# 05_FPGA_SOC_Part1.net
KiCad netlist of a schematic drawn in Altium Designer
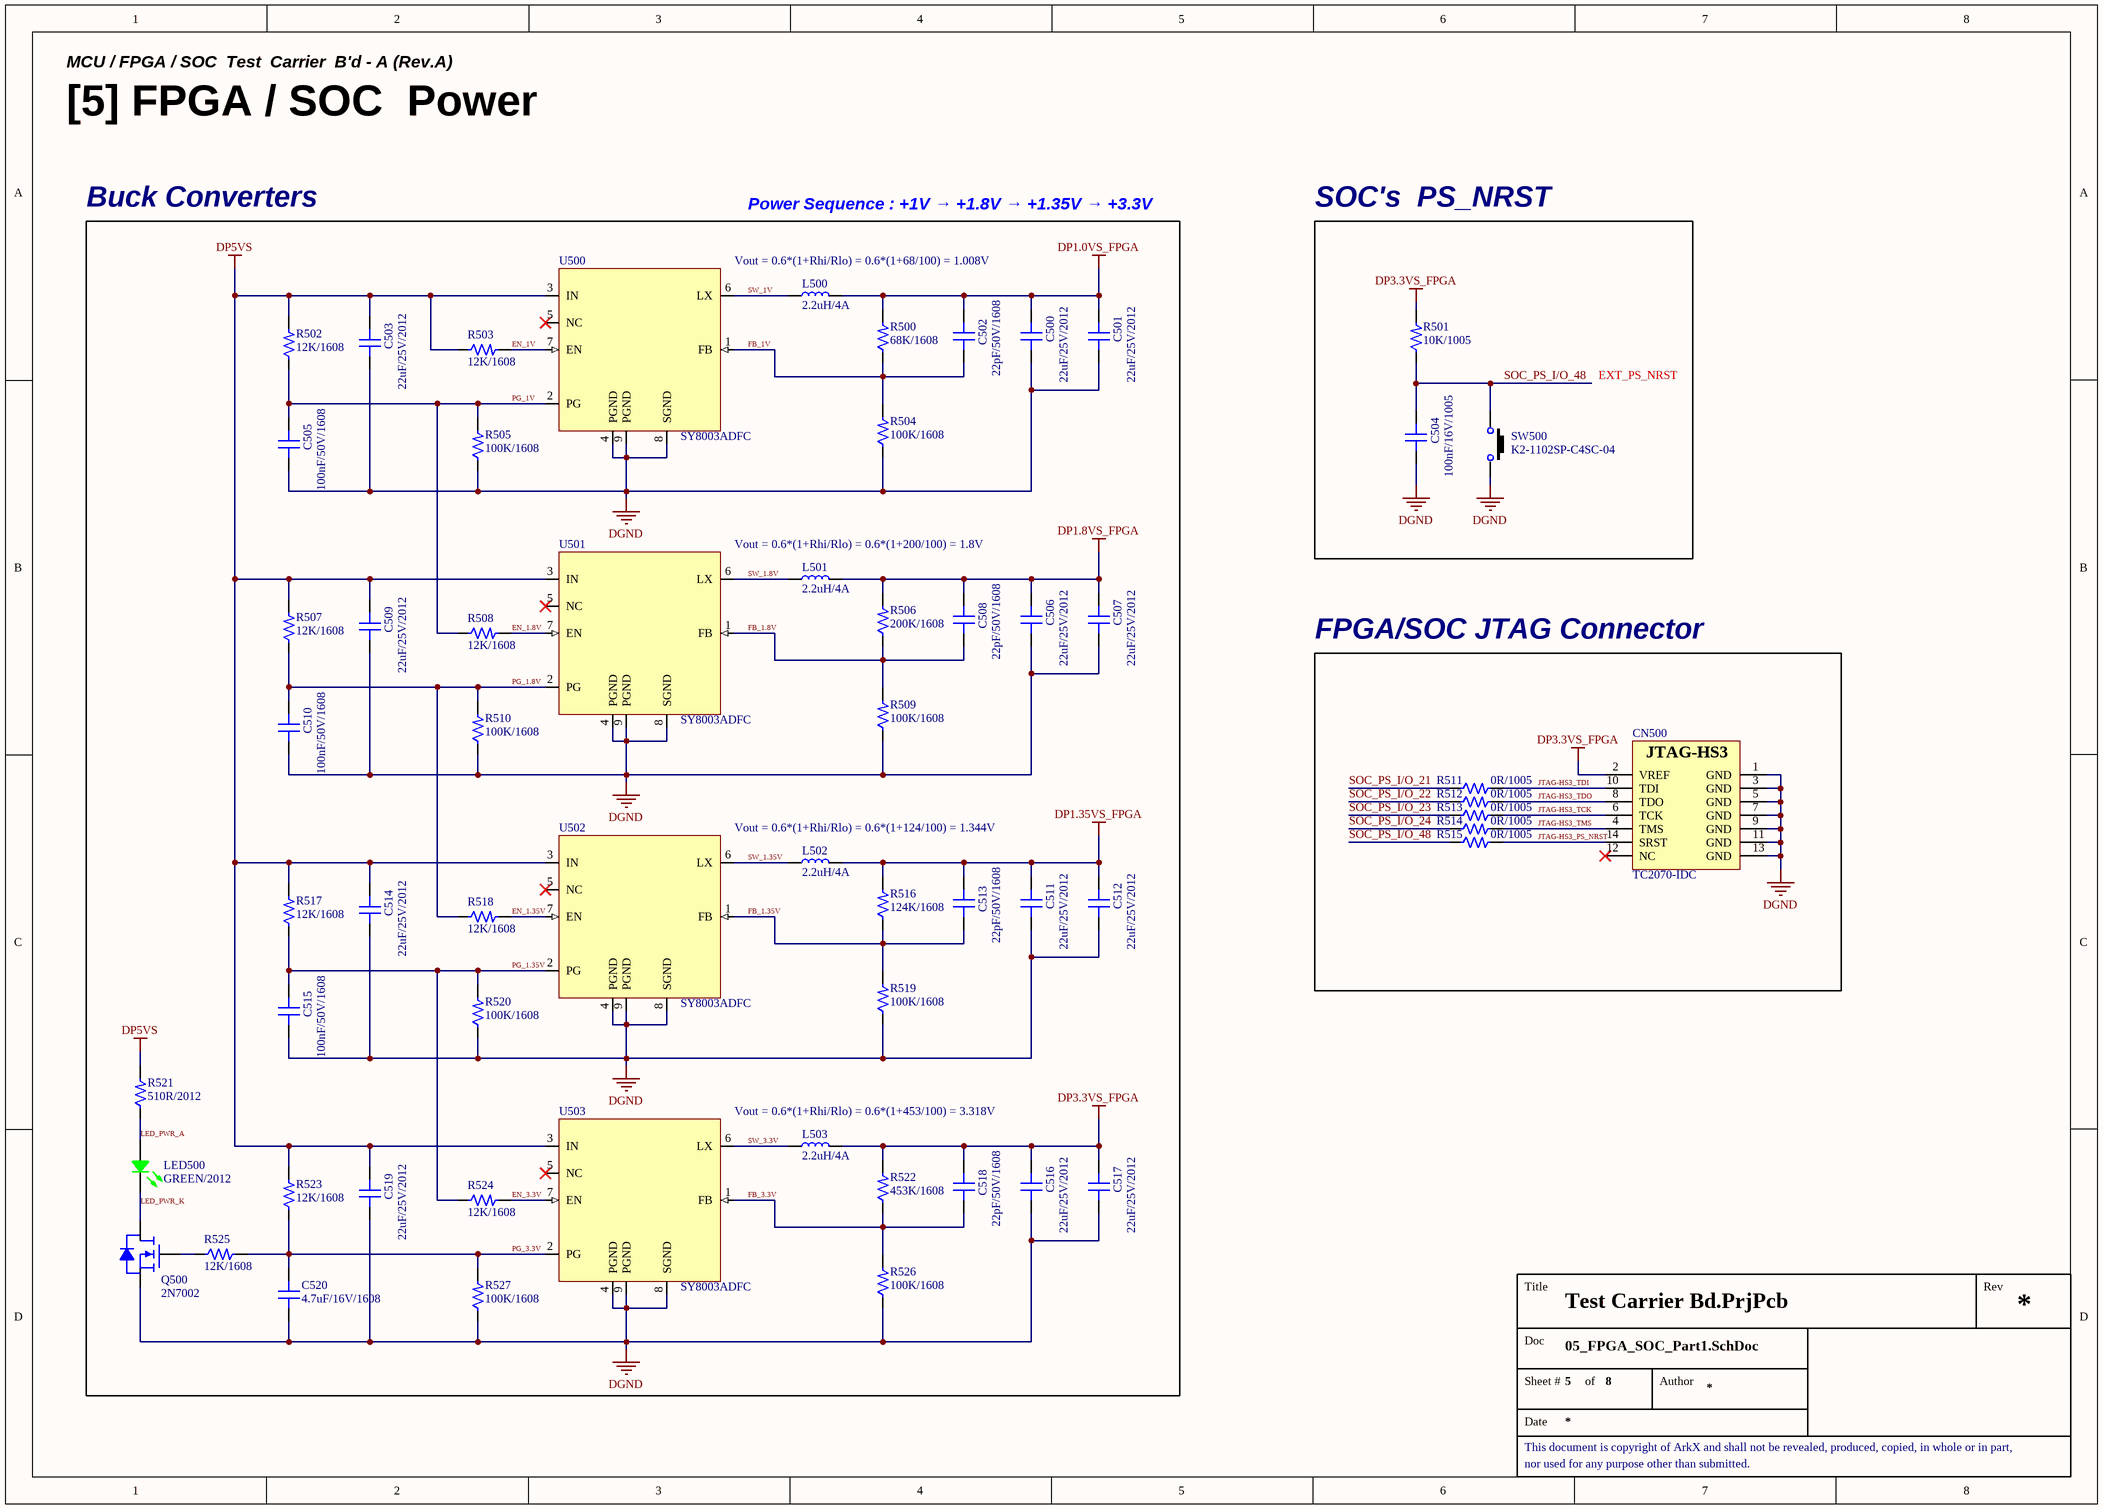
[diagram p0: 05_FPGA_SOC_Part1.SchDoc]

(export (version "E")
  (design (tool "Eeschema 10.0.6"))
  (components
    (comp (ref "C500")
      (value "22uF/25V/2012")
      (footprint "CAP 2012 (0805_INCH)")
      (description "Ceramic CAP_22uF/25V/2012")
      (fields (field (name "LCSC PART #") "C45783"))
      (libsource (lib "Arkx") (part "CAP_22uF/25V/2012"))
    )
    (comp (ref "C501")
      (value "22uF/25V/2012")
      (footprint "CAP 2012 (0805_INCH)")
      (description "Ceramic CAP_22uF/25V/2012")
      (fields (field (name "LCSC PART #") "C45783"))
      (libsource (lib "Arkx") (part "CAP_22uF/25V/2012"))
    )
    (comp (ref "C502")
      (value "22pF/50V/1608")
      (footprint "CAP 1608 (0603_INCH)")
      (description "Ceramic CAP_22pF/50V/1608")
      (fields (field (name "LCSC PART #") "C1653"))
      (libsource (lib "Arkx") (part "CAP_22pF/50V/1608"))
    )
    (comp (ref "C503")
      (value "22uF/25V/2012")
      (footprint "CAP 2012 (0805_INCH)")
      (description "Ceramic CAP_22uF/25V/2012")
      (fields (field (name "LCSC PART #") "C45783"))
      (libsource (lib "Arkx") (part "CAP_22uF/25V/2012"))
    )
    (comp (ref "C504")
      (value "100nF/16V/1005")
      (footprint "CAP 1005 (0402_INCH)")
      (description "Ceramic CAP_100nF/16V/1005")
      (fields (field (name "LCSC PART #") "C1525"))
      (libsource (lib "Arkx") (part "CAP_100nF/16V/1005"))
    )
    (comp (ref "C505")
      (value "100nF/50V/1608")
      (footprint "CAP 1608 (0603_INCH)")
      (description "Ceramic CAP_100nF/50V/1608")
      (fields (field (name "LCSC PART #") "C14663"))
      (libsource (lib "Arkx") (part "CAP_100nF/50V/1608"))
    )
    (comp (ref "C506")
      (value "22uF/25V/2012")
      (footprint "CAP 2012 (0805_INCH)")
      (description "Ceramic CAP_22uF/25V/2012")
      (fields (field (name "LCSC PART #") "C45783"))
      (libsource (lib "Arkx") (part "CAP_22uF/25V/2012"))
    )
    (comp (ref "C507")
      (value "22uF/25V/2012")
      (footprint "CAP 2012 (0805_INCH)")
      (description "Ceramic CAP_22uF/25V/2012")
      (fields (field (name "LCSC PART #") "C45783"))
      (libsource (lib "Arkx") (part "CAP_22uF/25V/2012"))
    )
    (comp (ref "C508")
      (value "22pF/50V/1608")
      (footprint "CAP 1608 (0603_INCH)")
      (description "Ceramic CAP_22pF/50V/1608")
      (fields (field (name "LCSC PART #") "C1653"))
      (libsource (lib "Arkx") (part "CAP_22pF/50V/1608"))
    )
    (comp (ref "C509")
      (value "22uF/25V/2012")
      (footprint "CAP 2012 (0805_INCH)")
      (description "Ceramic CAP_22uF/25V/2012")
      (fields (field (name "LCSC PART #") "C45783"))
      (libsource (lib "Arkx") (part "CAP_22uF/25V/2012"))
    )
    (comp (ref "C510")
      (value "100nF/50V/1608")
      (footprint "CAP 1608 (0603_INCH)")
      (description "Ceramic CAP_100nF/50V/1608")
      (fields (field (name "LCSC PART #") "C14663"))
      (libsource (lib "Arkx") (part "CAP_100nF/50V/1608"))
    )
    (comp (ref "C511")
      (value "22uF/25V/2012")
      (footprint "CAP 2012 (0805_INCH)")
      (description "Ceramic CAP_22uF/25V/2012")
      (fields (field (name "LCSC PART #") "C45783"))
      (libsource (lib "Arkx") (part "CAP_22uF/25V/2012"))
    )
    (comp (ref "C512")
      (value "22uF/25V/2012")
      (footprint "CAP 2012 (0805_INCH)")
      (description "Ceramic CAP_22uF/25V/2012")
      (fields (field (name "LCSC PART #") "C45783"))
      (libsource (lib "Arkx") (part "CAP_22uF/25V/2012"))
    )
    (comp (ref "C513")
      (value "22pF/50V/1608")
      (footprint "CAP 1608 (0603_INCH)")
      (description "Ceramic CAP_22pF/50V/1608")
      (fields (field (name "LCSC PART #") "C1653"))
      (libsource (lib "Arkx") (part "CAP_22pF/50V/1608"))
    )
    (comp (ref "C514")
      (value "22uF/25V/2012")
      (footprint "CAP 2012 (0805_INCH)")
      (description "Ceramic CAP_22uF/25V/2012")
      (fields (field (name "LCSC PART #") "C45783"))
      (libsource (lib "Arkx") (part "CAP_22uF/25V/2012"))
    )
    (comp (ref "C515")
      (value "100nF/50V/1608")
      (footprint "CAP 1608 (0603_INCH)")
      (description "Ceramic CAP_100nF/50V/1608")
      (fields (field (name "LCSC PART #") "C14663"))
      (libsource (lib "Arkx") (part "CAP_100nF/50V/1608"))
    )
    (comp (ref "C516")
      (value "22uF/25V/2012")
      (footprint "CAP 2012 (0805_INCH)")
      (description "Ceramic CAP_22uF/25V/2012")
      (fields (field (name "LCSC PART #") "C45783"))
      (libsource (lib "Arkx") (part "CAP_22uF/25V/2012"))
    )
    (comp (ref "C517")
      (value "22uF/25V/2012")
      (footprint "CAP 2012 (0805_INCH)")
      (description "Ceramic CAP_22uF/25V/2012")
      (fields (field (name "LCSC PART #") "C45783"))
      (libsource (lib "Arkx") (part "CAP_22uF/25V/2012"))
    )
    (comp (ref "C518")
      (value "22pF/50V/1608")
      (footprint "CAP 1608 (0603_INCH)")
      (description "Ceramic CAP_22pF/50V/1608")
      (fields (field (name "LCSC PART #") "C1653"))
      (libsource (lib "Arkx") (part "CAP_22pF/50V/1608"))
    )
    (comp (ref "C519")
      (value "22uF/25V/2012")
      (footprint "CAP 2012 (0805_INCH)")
      (description "Ceramic CAP_22uF/25V/2012")
      (fields (field (name "LCSC PART #") "C45783"))
      (libsource (lib "Arkx") (part "CAP_22uF/25V/2012"))
    )
    (comp (ref "C520")
      (value "4.7uF/16V/1608")
      (footprint "CAP 1608 (0603_INCH)")
      (description "Ceramic CAP_4.7uF/16V/1608")
      (fields (field (name "LCSC PART #") "C19666"))
      (libsource (lib "Arkx") (part "CAP_4.7uF/16V/1608"))
    )
    (comp (ref "CN500")
      (value "TC2070-IDC")
      (footprint "CON_TC2070-IDC")
      (description "TC2070 14-pin Plug-of-Nails™ (with legs) to 14 pin 2mm female IDC connector.")
      (libsource (lib "Arkx") (part "CON_TC2070-IDC(JTAG-HS3)"))
    )
    (comp (ref "L500")
      (value "2.2uH/4A")
      (footprint "IND_2.2uH/4A/6x6_(BWVS006060282R2M00)")
      (description "FIXED IND 2.2uH 4A 20mohm SMD")
      (fields (field (name "LCSC PART #") "C2838207"))
      (libsource (lib "Arkx") (part "IND_2.2uH/4A/6x6"))
    )
    (comp (ref "L501")
      (value "2.2uH/4A")
      (footprint "IND_2.2uH/4A/6x6_(BWVS006060282R2M00)")
      (description "FIXED IND 2.2uH 4A 20mohm SMD")
      (fields (field (name "LCSC PART #") "C2838207"))
      (libsource (lib "Arkx") (part "IND_2.2uH/4A/6x6"))
    )
    (comp (ref "L502")
      (value "2.2uH/4A")
      (footprint "IND_2.2uH/4A/6x6_(BWVS006060282R2M00)")
      (description "FIXED IND 2.2uH 4A 20mohm SMD")
      (fields (field (name "LCSC PART #") "C2838207"))
      (libsource (lib "Arkx") (part "IND_2.2uH/4A/6x6"))
    )
    (comp (ref "L503")
      (value "2.2uH/4A")
      (footprint "IND_2.2uH/4A/6x6_(BWVS006060282R2M00)")
      (description "FIXED IND 2.2uH 4A 20mohm SMD")
      (fields (field (name "LCSC PART #") "C2838207"))
      (libsource (lib "Arkx") (part "IND_2.2uH/4A/6x6"))
    )
    (comp (ref "LED500")
      (value "GREEN/2012")
      (footprint "LED MHT170RGBCT (GREEN)")
      (fields (field (name "LCSC PART #") "C2962094"))
      (libsource (lib "Arkx") (part "LED_MHT170RGBCT(GREEN)"))
    )
    (comp (ref "Q500")
      (value "2N7002")
      (footprint "SOT 23-3 (DIODES INCORPORATED)")
      (description "60V 115mA 200mW 7.5Ω@10V,500mA N Channel SOT-23  MOSFETs ROHS")
      (fields (field (name "LCSC PART #") "C8545"))
      (libsource (lib "Arkx") (part "FET_2N7002"))
    )
    (comp (ref "R500")
      (value "68K/1608")
      (footprint "RES 1608 (0603_inch)")
      (description "RES_68K/1608/0.1W")
      (fields (field (name "LCSC PART #") "C23231"))
      (libsource (lib "Arkx") (part "RES_68K/1608/0.1W"))
    )
    (comp (ref "R501")
      (value "10K/1005")
      (footprint "RES 1005 (0402_inch)")
      (description "RES_10K/1005/62.5mW")
      (fields (field (name "LCSC PART #") "C25744"))
      (libsource (lib "Arkx") (part "RES_10K/1005/62.5mW"))
    )
    (comp (ref "R502")
      (value "12K/1608")
      (footprint "RES 1608 (0603_inch)")
      (description "RES_12K/1608/0.1W")
      (fields (field (name "LCSC PART #") "C22790"))
      (libsource (lib "Arkx") (part "RES_12K/1608/0.1W"))
    )
    (comp (ref "R503")
      (value "12K/1608")
      (footprint "RES 1608 (0603_inch)")
      (description "RES_12K/1608/0.1W")
      (fields (field (name "LCSC PART #") "C22790"))
      (libsource (lib "Arkx") (part "RES_12K/1608/0.1W"))
    )
    (comp (ref "R504")
      (value "100K/1608")
      (footprint "RES 1608 (0603_inch)")
      (description "RES_100K/1608/0.1W")
      (fields (field (name "LCSC PART #") "C25803"))
      (libsource (lib "Arkx") (part "RES_100K/1608/0.1W"))
    )
    (comp (ref "R505")
      (value "100K/1608")
      (footprint "RES 1608 (0603_inch)")
      (description "RES_100K/1608/0.1W")
      (fields (field (name "LCSC PART #") "C25803"))
      (libsource (lib "Arkx") (part "RES_100K/1608/0.1W"))
    )
    (comp (ref "R506")
      (value "200K/1608")
      (footprint "RES 1608 (0603_inch)")
      (description "RES_200K/1608/0.1W")
      (fields (field (name "LCSC PART #") "C25811"))
      (libsource (lib "Arkx") (part "RES_200K/1608/0.1W"))
    )
    (comp (ref "R507")
      (value "12K/1608")
      (footprint "RES 1608 (0603_inch)")
      (description "RES_12K/1608/0.1W")
      (fields (field (name "LCSC PART #") "C22790"))
      (libsource (lib "Arkx") (part "RES_12K/1608/0.1W"))
    )
    (comp (ref "R508")
      (value "12K/1608")
      (footprint "RES 1608 (0603_inch)")
      (description "RES_12K/1608/0.1W")
      (fields (field (name "LCSC PART #") "C22790"))
      (libsource (lib "Arkx") (part "RES_12K/1608/0.1W"))
    )
    (comp (ref "R509")
      (value "100K/1608")
      (footprint "RES 1608 (0603_inch)")
      (description "RES_100K/1608/0.1W")
      (fields (field (name "LCSC PART #") "C25803"))
      (libsource (lib "Arkx") (part "RES_100K/1608/0.1W"))
    )
    (comp (ref "R510")
      (value "100K/1608")
      (footprint "RES 1608 (0603_inch)")
      (description "RES_100K/1608/0.1W")
      (fields (field (name "LCSC PART #") "C25803"))
      (libsource (lib "Arkx") (part "RES_100K/1608/0.1W"))
    )
    (comp (ref "R511")
      (value "0R/1005")
      (footprint "RES 1005 (0402_inch)")
      (description "RES_0R/1005/62.5mW")
      (fields (field (name "LCSC PART #") "C17168"))
      (libsource (lib "Arkx") (part "RES_0R/1005/62.5mW"))
    )
    (comp (ref "R512")
      (value "0R/1005")
      (footprint "RES 1005 (0402_inch)")
      (description "RES_0R/1005/62.5mW")
      (fields (field (name "LCSC PART #") "C17168"))
      (libsource (lib "Arkx") (part "RES_0R/1005/62.5mW"))
    )
    (comp (ref "R513")
      (value "0R/1005")
      (footprint "RES 1005 (0402_inch)")
      (description "RES_0R/1005/62.5mW")
      (fields (field (name "LCSC PART #") "C17168"))
      (libsource (lib "Arkx") (part "RES_0R/1005/62.5mW"))
    )
    (comp (ref "R514")
      (value "0R/1005")
      (footprint "RES 1005 (0402_inch)")
      (description "RES_0R/1005/62.5mW")
      (fields (field (name "LCSC PART #") "C17168"))
      (libsource (lib "Arkx") (part "RES_0R/1005/62.5mW"))
    )
    (comp (ref "R515")
      (value "0R/1005")
      (footprint "RES 1005 (0402_inch)")
      (description "RES_0R/1005/62.5mW")
      (fields (field (name "LCSC PART #") "C17168"))
      (libsource (lib "Arkx") (part "RES_0R/1005/62.5mW"))
    )
    (comp (ref "R516")
      (value "124K/1608")
      (footprint "RES 1608 (0603_inch)")
      (description "RES_124K/1608/0.1W")
      (fields (field (name "LCSC PART #") "C140118"))
      (libsource (lib "Arkx") (part "RES_124K/1608/0.1W"))
    )
    (comp (ref "R517")
      (value "12K/1608")
      (footprint "RES 1608 (0603_inch)")
      (description "RES_12K/1608/0.1W")
      (fields (field (name "LCSC PART #") "C22790"))
      (libsource (lib "Arkx") (part "RES_12K/1608/0.1W"))
    )
    (comp (ref "R518")
      (value "12K/1608")
      (footprint "RES 1608 (0603_inch)")
      (description "RES_12K/1608/0.1W")
      (fields (field (name "LCSC PART #") "C22790"))
      (libsource (lib "Arkx") (part "RES_12K/1608/0.1W"))
    )
    (comp (ref "R519")
      (value "100K/1608")
      (footprint "RES 1608 (0603_inch)")
      (description "RES_100K/1608/0.1W")
      (fields (field (name "LCSC PART #") "C25803"))
      (libsource (lib "Arkx") (part "RES_100K/1608/0.1W"))
    )
    (comp (ref "R520")
      (value "100K/1608")
      (footprint "RES 1608 (0603_inch)")
      (description "RES_100K/1608/0.1W")
      (fields (field (name "LCSC PART #") "C25803"))
      (libsource (lib "Arkx") (part "RES_100K/1608/0.1W"))
    )
    (comp (ref "R521")
      (value "510R/2012")
      (footprint "RES 2012 (0805_inch)")
      (description "RES_510R/2012/0.125W")
      (fields (field (name "LCSC PART #") "C17734"))
      (libsource (lib "Arkx") (part "RES_510R/2012/0.125W"))
    )
    (comp (ref "R522")
      (value "453K/1608")
      (footprint "RES 1608 (0603_inch)")
      (description "RES_453K/1608/0.1W")
      (fields (field (name "LCSC PART #") "C25818"))
      (libsource (lib "Arkx") (part "RES_453K/1608/0.1W"))
    )
    (comp (ref "R523")
      (value "12K/1608")
      (footprint "RES 1608 (0603_inch)")
      (description "RES_12K/1608/0.1W")
      (fields (field (name "LCSC PART #") "C22790"))
      (libsource (lib "Arkx") (part "RES_12K/1608/0.1W"))
    )
    (comp (ref "R524")
      (value "12K/1608")
      (footprint "RES 1608 (0603_inch)")
      (description "RES_12K/1608/0.1W")
      (fields (field (name "LCSC PART #") "C22790"))
      (libsource (lib "Arkx") (part "RES_12K/1608/0.1W"))
    )
    (comp (ref "R525")
      (value "12K/1608")
      (footprint "RES 1608 (0603_inch)")
      (description "RES_12K/1608/0.1W")
      (fields (field (name "LCSC PART #") "C22790"))
      (libsource (lib "Arkx") (part "RES_12K/1608/0.1W"))
    )
    (comp (ref "R526")
      (value "100K/1608")
      (footprint "RES 1608 (0603_inch)")
      (description "RES_100K/1608/0.1W")
      (fields (field (name "LCSC PART #") "C25803"))
      (libsource (lib "Arkx") (part "RES_100K/1608/0.1W"))
    )
    (comp (ref "R527")
      (value "100K/1608")
      (footprint "RES 1608 (0603_inch)")
      (description "RES_100K/1608/0.1W")
      (fields (field (name "LCSC PART #") "C25803"))
      (libsource (lib "Arkx") (part "RES_100K/1608/0.1W"))
    )
    (comp (ref "SW500")
      (value "K2-1102SP-C4SC-04")
      (footprint "SW K2-1102SP-C4SC-04")
      (fields (field (name "LCSC PART #") "C127509"))
      (libsource (lib "Arkx") (part "SW_K2-1102SP-C4SC-04(2P)"))
    )
    (comp (ref "U500")
      (value "SY8003ADFC")
      (footprint "IC_DFN_2X2_8L")
      (description "High Efficiency 5.5V, 3A Continuous, 1MHz Synchronous Step Down Regulator")
      (fields
        (field (name "MANUFACTURER") "Silergy")
        (field (name "MANUFACTURER PART NUMBER") "High Efficiency 5.5V, 3A continuous, 1MHz")
      )
      (libsource (lib "Arkx") (part "IC_REG_SY8003ADFC"))
    )
    (comp (ref "U501")
      (value "SY8003ADFC")
      (footprint "IC_DFN_2X2_8L")
      (description "High Efficiency 5.5V, 3A Continuous, 1MHz Synchronous Step Down Regulator")
      (fields
        (field (name "MANUFACTURER") "Silergy")
        (field (name "MANUFACTURER PART NUMBER") "High Efficiency 5.5V, 3A continuous, 1MHz")
      )
      (libsource (lib "Arkx") (part "IC_REG_SY8003ADFC"))
    )
    (comp (ref "U502")
      (value "SY8003ADFC")
      (footprint "IC_DFN_2X2_8L")
      (description "High Efficiency 5.5V, 3A Continuous, 1MHz Synchronous Step Down Regulator")
      (fields
        (field (name "MANUFACTURER") "Silergy")
        (field (name "MANUFACTURER PART NUMBER") "High Efficiency 5.5V, 3A continuous, 1MHz")
      )
      (libsource (lib "Arkx") (part "IC_REG_SY8003ADFC"))
    )
    (comp (ref "U503")
      (value "SY8003ADFC")
      (footprint "IC_DFN_2X2_8L")
      (description "High Efficiency 5.5V, 3A Continuous, 1MHz Synchronous Step Down Regulator")
      (fields
        (field (name "MANUFACTURER") "Silergy")
        (field (name "MANUFACTURER PART NUMBER") "High Efficiency 5.5V, 3A continuous, 1MHz")
      )
      (libsource (lib "Arkx") (part "IC_REG_SY8003ADFC"))
    )
  )
  (nets
    (net (code "1") (name "/EN_1.8V") (class "Default")
      (node (ref "R508") (pin "2") (pinfunction "2_2") (pintype "passive"))
      (node (ref "U501") (pin "7") (pinfunction "EN_7") (pintype "input"))
    )
    (net (code "2") (name "/EN_1.35V") (class "Default")
      (node (ref "R518") (pin "2") (pinfunction "2_2") (pintype "passive"))
      (node (ref "U502") (pin "7") (pinfunction "EN_7") (pintype "input"))
    )
    (net (code "3") (name "/EN_1V") (class "Default")
      (node (ref "R503") (pin "2") (pinfunction "2_2") (pintype "passive"))
      (node (ref "U500") (pin "7") (pinfunction "EN_7") (pintype "input"))
    )
    (net (code "4") (name "/EN_3.3V") (class "Default")
      (node (ref "R524") (pin "2") (pinfunction "2_2") (pintype "passive"))
      (node (ref "U503") (pin "7") (pinfunction "EN_7") (pintype "input"))
    )
    (net (code "5") (name "/FB_1.8V") (class "Default")
      (node (ref "C508") (pin "1") (pinfunction "1_1") (pintype "passive"))
      (node (ref "R506") (pin "1") (pinfunction "1_1") (pintype "passive"))
      (node (ref "R509") (pin "2") (pinfunction "2_2") (pintype "passive"))
      (node (ref "U501") (pin "1") (pinfunction "FB_1") (pintype "input"))
    )
    (net (code "6") (name "/FB_1.35V") (class "Default")
      (node (ref "C513") (pin "1") (pinfunction "1_1") (pintype "passive"))
      (node (ref "R516") (pin "1") (pinfunction "1_1") (pintype "passive"))
      (node (ref "R519") (pin "2") (pinfunction "2_2") (pintype "passive"))
      (node (ref "U502") (pin "1") (pinfunction "FB_1") (pintype "input"))
    )
    (net (code "7") (name "/FB_1V") (class "Default")
      (node (ref "C502") (pin "1") (pinfunction "1_1") (pintype "passive"))
      (node (ref "R500") (pin "1") (pinfunction "1_1") (pintype "passive"))
      (node (ref "R504") (pin "2") (pinfunction "2_2") (pintype "passive"))
      (node (ref "U500") (pin "1") (pinfunction "FB_1") (pintype "input"))
    )
    (net (code "8") (name "/FB_3.3V") (class "Default")
      (node (ref "C518") (pin "1") (pinfunction "1_1") (pintype "passive"))
      (node (ref "R522") (pin "1") (pinfunction "1_1") (pintype "passive"))
      (node (ref "R526") (pin "2") (pinfunction "2_2") (pintype "passive"))
      (node (ref "U503") (pin "1") (pinfunction "FB_1") (pintype "input"))
    )
    (net (code "9") (name "/JTAG-HS3_PS_NRST") (class "Default")
      (node (ref "CN500") (pin "14") (pinfunction "SRST_14") (pintype "passive"))
      (node (ref "R515") (pin "2") (pinfunction "2_2") (pintype "passive"))
    )
    (net (code "10") (name "/JTAG-HS3_TCK") (class "Default")
      (node (ref "CN500") (pin "6") (pinfunction "TCK_6") (pintype "passive"))
      (node (ref "R513") (pin "2") (pinfunction "2_2") (pintype "passive"))
    )
    (net (code "11") (name "/JTAG-HS3_TDI") (class "Default")
      (node (ref "CN500") (pin "10") (pinfunction "TDI_10") (pintype "passive"))
      (node (ref "R511") (pin "2") (pinfunction "2_2") (pintype "passive"))
    )
    (net (code "12") (name "/JTAG-HS3_TDO") (class "Default")
      (node (ref "CN500") (pin "8") (pinfunction "TDO_8") (pintype "passive"))
      (node (ref "R512") (pin "2") (pinfunction "2_2") (pintype "passive"))
    )
    (net (code "13") (name "/JTAG-HS3_TMS") (class "Default")
      (node (ref "CN500") (pin "4") (pinfunction "TMS_4") (pintype "passive"))
      (node (ref "R514") (pin "2") (pinfunction "2_2") (pintype "passive"))
    )
    (net (code "14") (name "/LED_PWR_A") (class "Default")
      (node (ref "LED500") (pin "4") (pinfunction "Common_Anode_4") (pintype "passive"))
      (node (ref "R521") (pin "1") (pinfunction "1_1") (pintype "passive"))
    )
    (net (code "15") (name "/LED_PWR_K") (class "Default")
      (node (ref "LED500") (pin "2") (pinfunction "GREEN_2") (pintype "passive"))
      (node (ref "Q500") (pin "3") (pinfunction "D_3") (pintype "passive"))
    )
    (net (code "16") (name "/PG_1.8V") (class "Default")
      (node (ref "C510") (pin "2") (pinfunction "2_2") (pintype "passive"))
      (node (ref "R507") (pin "1") (pinfunction "1_1") (pintype "passive"))
      (node (ref "R510") (pin "2") (pinfunction "2_2") (pintype "passive"))
      (node (ref "R518") (pin "1") (pinfunction "1_1") (pintype "passive"))
      (node (ref "U501") (pin "2") (pinfunction "PG_2") (pintype "open_collector"))
    )
    (net (code "17") (name "/PG_1.35V") (class "Default")
      (node (ref "C515") (pin "2") (pinfunction "2_2") (pintype "passive"))
      (node (ref "R517") (pin "1") (pinfunction "1_1") (pintype "passive"))
      (node (ref "R520") (pin "2") (pinfunction "2_2") (pintype "passive"))
      (node (ref "R524") (pin "1") (pinfunction "1_1") (pintype "passive"))
      (node (ref "U502") (pin "2") (pinfunction "PG_2") (pintype "open_collector"))
    )
    (net (code "18") (name "/PG_1V") (class "Default")
      (node (ref "C505") (pin "2") (pinfunction "2_2") (pintype "passive"))
      (node (ref "R502") (pin "1") (pinfunction "1_1") (pintype "passive"))
      (node (ref "R505") (pin "2") (pinfunction "2_2") (pintype "passive"))
      (node (ref "R508") (pin "1") (pinfunction "1_1") (pintype "passive"))
      (node (ref "U500") (pin "2") (pinfunction "PG_2") (pintype "open_collector"))
    )
    (net (code "19") (name "/PG_3.3V") (class "Default")
      (node (ref "C520") (pin "2") (pinfunction "2_2") (pintype "passive"))
      (node (ref "R523") (pin "1") (pinfunction "1_1") (pintype "passive"))
      (node (ref "R525") (pin "2") (pinfunction "2_2") (pintype "passive"))
      (node (ref "R527") (pin "2") (pinfunction "2_2") (pintype "passive"))
      (node (ref "U503") (pin "2") (pinfunction "PG_2") (pintype "open_collector"))
    )
    (net (code "20") (name "/SOC_PS_I{slash}O_21") (class "Default")
      (node (ref "R511") (pin "1") (pinfunction "1_1") (pintype "passive"))
    )
    (net (code "21") (name "/SOC_PS_I{slash}O_22") (class "Default")
      (node (ref "R512") (pin "1") (pinfunction "1_1") (pintype "passive"))
    )
    (net (code "22") (name "/SOC_PS_I{slash}O_23") (class "Default")
      (node (ref "R513") (pin "1") (pinfunction "1_1") (pintype "passive"))
    )
    (net (code "23") (name "/SOC_PS_I{slash}O_24") (class "Default")
      (node (ref "R514") (pin "1") (pinfunction "1_1") (pintype "passive"))
    )
    (net (code "24") (name "/SOC_PS_I{slash}O_48") (class "Default")
      (node (ref "C504") (pin "2") (pinfunction "2_2") (pintype "passive"))
      (node (ref "R501") (pin "1") (pinfunction "1_1") (pintype "passive"))
      (node (ref "R515") (pin "1") (pinfunction "1_1") (pintype "passive"))
      (node (ref "SW500") (pin "1") (pinfunction "1_1") (pintype "passive"))
    )
    (net (code "25") (name "/SW_1.8V") (class "Default")
      (node (ref "L501") (pin "1") (pinfunction "1_1") (pintype "passive"))
      (node (ref "U501") (pin "6") (pinfunction "LX_6") (pintype "power_in"))
    )
    (net (code "26") (name "/SW_1.35V") (class "Default")
      (node (ref "L502") (pin "1") (pinfunction "1_1") (pintype "passive"))
      (node (ref "U502") (pin "6") (pinfunction "LX_6") (pintype "power_in"))
    )
    (net (code "27") (name "/SW_1V") (class "Default")
      (node (ref "L500") (pin "1") (pinfunction "1_1") (pintype "passive"))
      (node (ref "U500") (pin "6") (pinfunction "LX_6") (pintype "power_in"))
    )
    (net (code "28") (name "/SW_3.3V") (class "Default")
      (node (ref "L503") (pin "1") (pinfunction "1_1") (pintype "passive"))
      (node (ref "U503") (pin "6") (pinfunction "LX_6") (pintype "power_in"))
    )
    (net (code "29") (name "DGND") (class "Default")
      (node (ref "C500") (pin "1") (pinfunction "1_1") (pintype "passive"))
      (node (ref "C501") (pin "1") (pinfunction "1_1") (pintype "passive"))
      (node (ref "C503") (pin "1") (pinfunction "1_1") (pintype "passive"))
      (node (ref "C504") (pin "1") (pinfunction "1_1") (pintype "passive"))
      (node (ref "C505") (pin "1") (pinfunction "1_1") (pintype "passive"))
      (node (ref "C506") (pin "1") (pinfunction "1_1") (pintype "passive"))
      (node (ref "C507") (pin "1") (pinfunction "1_1") (pintype "passive"))
      (node (ref "C509") (pin "1") (pinfunction "1_1") (pintype "passive"))
      (node (ref "C510") (pin "1") (pinfunction "1_1") (pintype "passive"))
      (node (ref "C511") (pin "1") (pinfunction "1_1") (pintype "passive"))
      (node (ref "C512") (pin "1") (pinfunction "1_1") (pintype "passive"))
      (node (ref "C514") (pin "1") (pinfunction "1_1") (pintype "passive"))
      (node (ref "C515") (pin "1") (pinfunction "1_1") (pintype "passive"))
      (node (ref "C516") (pin "1") (pinfunction "1_1") (pintype "passive"))
      (node (ref "C517") (pin "1") (pinfunction "1_1") (pintype "passive"))
      (node (ref "C519") (pin "1") (pinfunction "1_1") (pintype "passive"))
      (node (ref "C520") (pin "1") (pinfunction "1_1") (pintype "passive"))
      (node (ref "CN500") (pin "1") (pinfunction "GND_1") (pintype "passive"))
      (node (ref "CN500") (pin "11") (pinfunction "GND_11") (pintype "passive"))
      (node (ref "CN500") (pin "13") (pinfunction "GND_13") (pintype "passive"))
      (node (ref "CN500") (pin "3") (pinfunction "GND_3") (pintype "passive"))
      (node (ref "CN500") (pin "5") (pinfunction "GND_5") (pintype "passive"))
      (node (ref "CN500") (pin "7") (pinfunction "GND_7") (pintype "passive"))
      (node (ref "CN500") (pin "9") (pinfunction "GND_9") (pintype "passive"))
      (node (ref "Q500") (pin "2") (pinfunction "S_2") (pintype "passive"))
      (node (ref "R504") (pin "1") (pinfunction "1_1") (pintype "passive"))
      (node (ref "R505") (pin "1") (pinfunction "1_1") (pintype "passive"))
      (node (ref "R509") (pin "1") (pinfunction "1_1") (pintype "passive"))
      (node (ref "R510") (pin "1") (pinfunction "1_1") (pintype "passive"))
      (node (ref "R519") (pin "1") (pinfunction "1_1") (pintype "passive"))
      (node (ref "R520") (pin "1") (pinfunction "1_1") (pintype "passive"))
      (node (ref "R526") (pin "1") (pinfunction "1_1") (pintype "passive"))
      (node (ref "R527") (pin "1") (pinfunction "1_1") (pintype "passive"))
      (node (ref "SW500") (pin "3") (pinfunction "3_3") (pintype "passive"))
      (node (ref "U500") (pin "4") (pinfunction "PGND_4") (pintype "power_in"))
      (node (ref "U500") (pin "8") (pinfunction "SGND_8") (pintype "power_in"))
      (node (ref "U500") (pin "9") (pinfunction "PGND_9") (pintype "power_in"))
      (node (ref "U501") (pin "4") (pinfunction "PGND_4") (pintype "power_in"))
      (node (ref "U501") (pin "8") (pinfunction "SGND_8") (pintype "power_in"))
      (node (ref "U501") (pin "9") (pinfunction "PGND_9") (pintype "power_in"))
      (node (ref "U502") (pin "4") (pinfunction "PGND_4") (pintype "power_in"))
      (node (ref "U502") (pin "8") (pinfunction "SGND_8") (pintype "power_in"))
      (node (ref "U502") (pin "9") (pinfunction "PGND_9") (pintype "power_in"))
      (node (ref "U503") (pin "4") (pinfunction "PGND_4") (pintype "power_in"))
      (node (ref "U503") (pin "8") (pinfunction "SGND_8") (pintype "power_in"))
      (node (ref "U503") (pin "9") (pinfunction "PGND_9") (pintype "power_in"))
    )
    (net (code "30") (name "DP1.0VS_FPGA") (class "Default")
      (node (ref "C500") (pin "2") (pinfunction "2_2") (pintype "passive"))
      (node (ref "C501") (pin "2") (pinfunction "2_2") (pintype "passive"))
      (node (ref "C502") (pin "2") (pinfunction "2_2") (pintype "passive"))
      (node (ref "L500") (pin "2") (pinfunction "2_2") (pintype "passive"))
      (node (ref "R500") (pin "2") (pinfunction "2_2") (pintype "passive"))
    )
    (net (code "31") (name "DP1.8VS_FPGA") (class "Default")
      (node (ref "C506") (pin "2") (pinfunction "2_2") (pintype "passive"))
      (node (ref "C507") (pin "2") (pinfunction "2_2") (pintype "passive"))
      (node (ref "C508") (pin "2") (pinfunction "2_2") (pintype "passive"))
      (node (ref "L501") (pin "2") (pinfunction "2_2") (pintype "passive"))
      (node (ref "R506") (pin "2") (pinfunction "2_2") (pintype "passive"))
    )
    (net (code "32") (name "DP1.35VS_FPGA") (class "Default")
      (node (ref "C511") (pin "2") (pinfunction "2_2") (pintype "passive"))
      (node (ref "C512") (pin "2") (pinfunction "2_2") (pintype "passive"))
      (node (ref "C513") (pin "2") (pinfunction "2_2") (pintype "passive"))
      (node (ref "L502") (pin "2") (pinfunction "2_2") (pintype "passive"))
      (node (ref "R516") (pin "2") (pinfunction "2_2") (pintype "passive"))
    )
    (net (code "33") (name "DP3.3VS_FPGA") (class "Default")
      (node (ref "C516") (pin "2") (pinfunction "2_2") (pintype "passive"))
      (node (ref "C517") (pin "2") (pinfunction "2_2") (pintype "passive"))
      (node (ref "C518") (pin "2") (pinfunction "2_2") (pintype "passive"))
      (node (ref "CN500") (pin "2") (pinfunction "VREF_2") (pintype "passive"))
      (node (ref "L503") (pin "2") (pinfunction "2_2") (pintype "passive"))
      (node (ref "R501") (pin "2") (pinfunction "2_2") (pintype "passive"))
      (node (ref "R522") (pin "2") (pinfunction "2_2") (pintype "passive"))
    )
    (net (code "34") (name "DP5VS") (class "Default")
      (node (ref "C503") (pin "2") (pinfunction "2_2") (pintype "passive"))
      (node (ref "C509") (pin "2") (pinfunction "2_2") (pintype "passive"))
      (node (ref "C514") (pin "2") (pinfunction "2_2") (pintype "passive"))
      (node (ref "C519") (pin "2") (pinfunction "2_2") (pintype "passive"))
      (node (ref "R502") (pin "2") (pinfunction "2_2") (pintype "passive"))
      (node (ref "R503") (pin "1") (pinfunction "1_1") (pintype "passive"))
      (node (ref "R507") (pin "2") (pinfunction "2_2") (pintype "passive"))
      (node (ref "R517") (pin "2") (pinfunction "2_2") (pintype "passive"))
      (node (ref "R521") (pin "2") (pinfunction "2_2") (pintype "passive"))
      (node (ref "R523") (pin "2") (pinfunction "2_2") (pintype "passive"))
      (node (ref "U500") (pin "3") (pinfunction "IN_3") (pintype "power_in"))
      (node (ref "U501") (pin "3") (pinfunction "IN_3") (pintype "power_in"))
      (node (ref "U502") (pin "3") (pinfunction "IN_3") (pintype "power_in"))
      (node (ref "U503") (pin "3") (pinfunction "IN_3") (pintype "power_in"))
    )
    (net (code "35") (name "Net-(Q500-G)") (class "Default")
      (node (ref "Q500") (pin "1") (pinfunction "G_1") (pintype "passive"))
      (node (ref "R525") (pin "1") (pinfunction "1_1") (pintype "passive"))
    )
    (net (code "36") (name "unconnected-(CN500-NC-Pad12)") (class "Default")
      (node (ref "CN500") (pin "12") (pinfunction "NC_12") (pintype "passive+no_connect"))
    )
    (net (code "37") (name "unconnected-(U500-NC-Pad5)") (class "Default")
      (node (ref "U500") (pin "5") (pinfunction "NC_5") (pintype "passive+no_connect"))
    )
    (net (code "38") (name "unconnected-(U501-NC-Pad5)") (class "Default")
      (node (ref "U501") (pin "5") (pinfunction "NC_5") (pintype "passive+no_connect"))
    )
    (net (code "39") (name "unconnected-(U502-NC-Pad5)") (class "Default")
      (node (ref "U502") (pin "5") (pinfunction "NC_5") (pintype "passive+no_connect"))
    )
    (net (code "40") (name "unconnected-(U503-NC-Pad5)") (class "Default")
      (node (ref "U503") (pin "5") (pinfunction "NC_5") (pintype "passive+no_connect"))
    )
  )
)
